# UWB_AOA_with_Display_STM32F103C8T6_V1_1.net
KiCad netlist of a schematic drawn in EAGLE
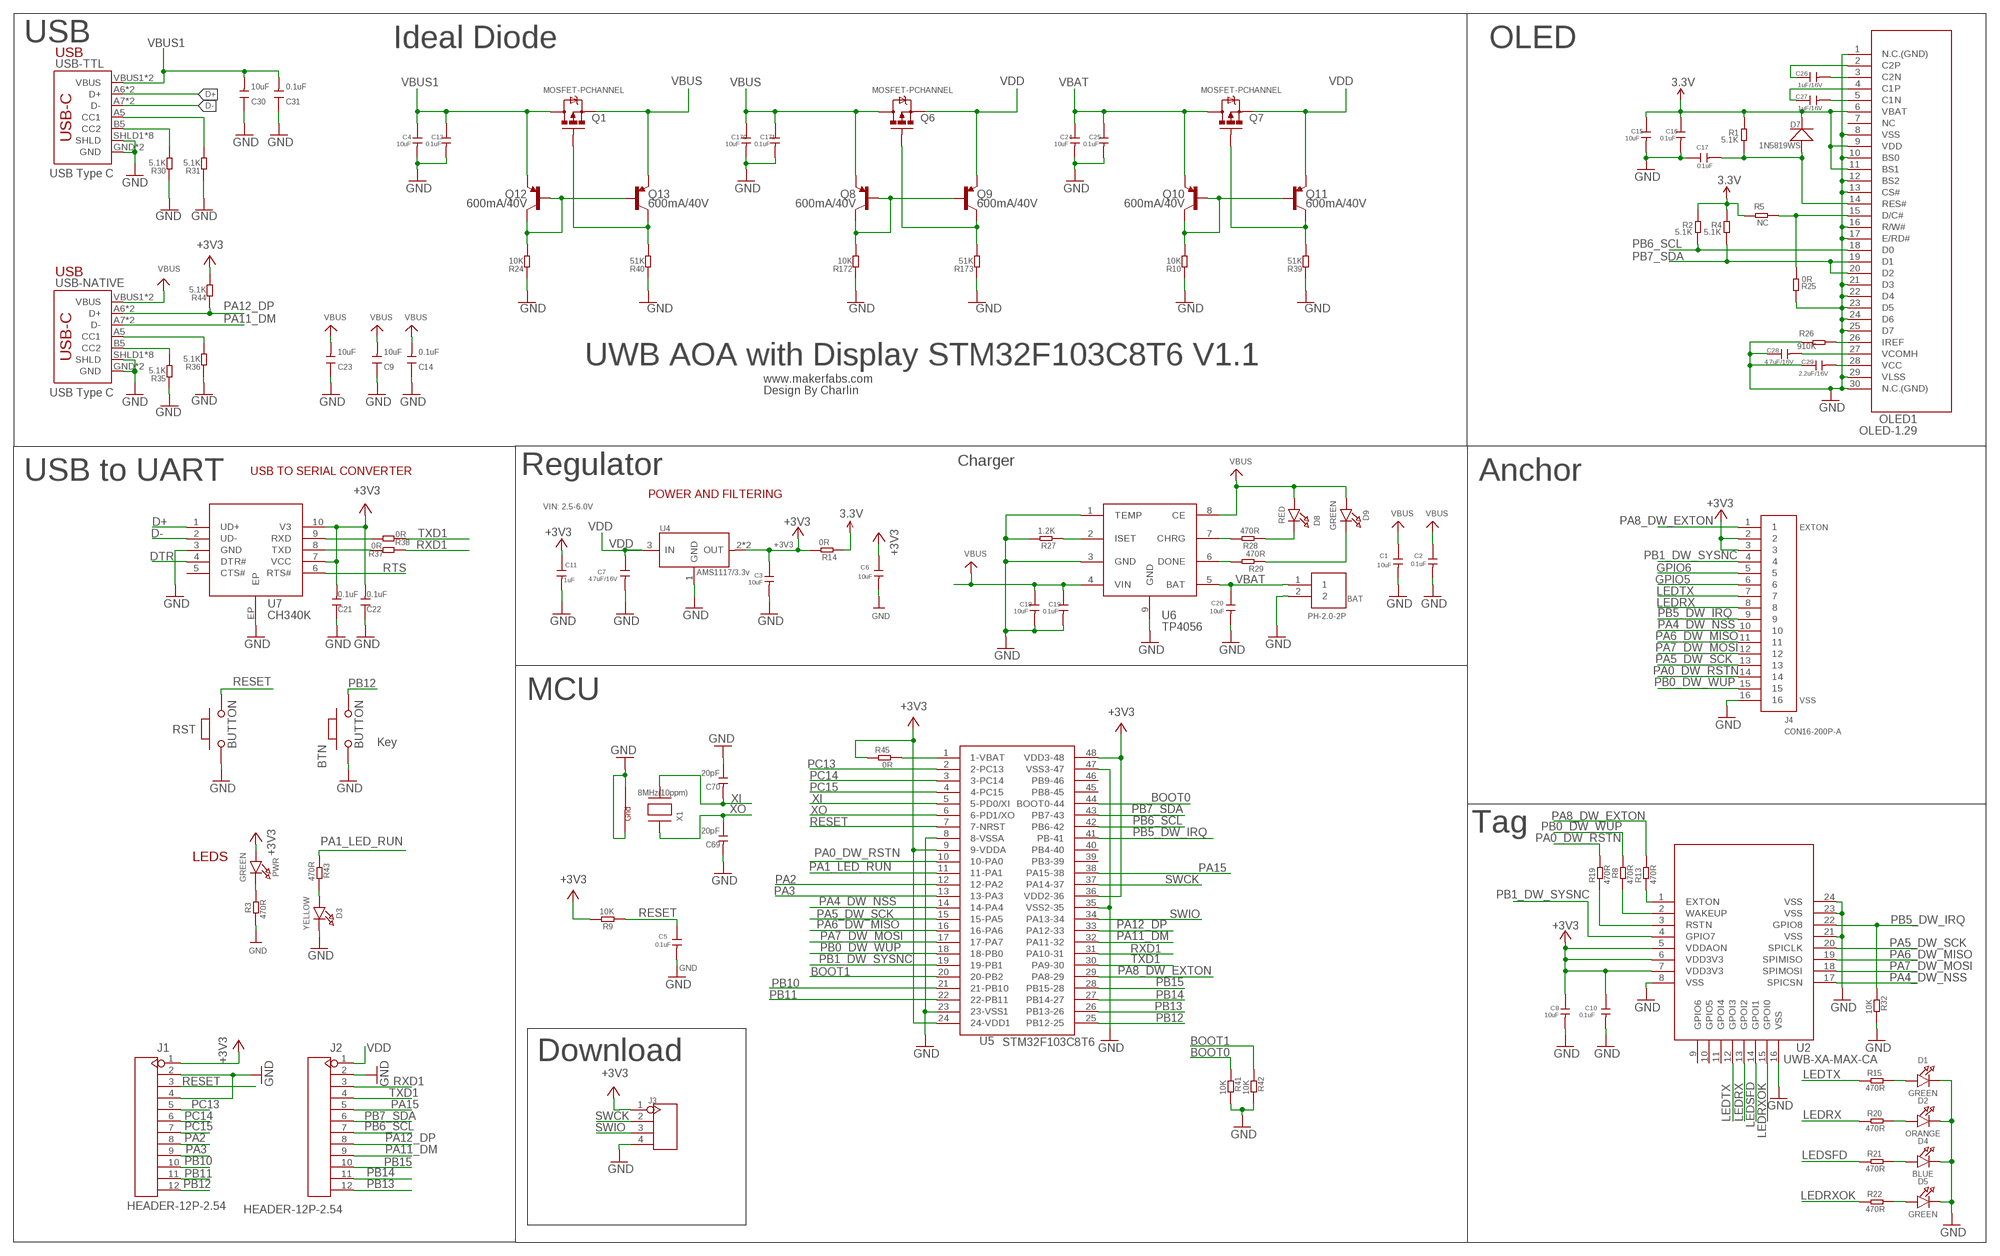
[diagram p0: schematic, sheet 1]

(export (version "E")
  (design (tool "Eeschema 10.0.6"))
  (components
    (comp (ref "BAT")
      (value "PH-2.0-2P")
      (footprint "eagle-import:PH-2.0-2P")
      (libsource (lib "eagle-import") (part "PH-2.0-2P"))
    )
    (comp (ref "BTN")
      (value "BUTTON")
      (footprint "eagle-import:157SW")
      (libsource (lib "eagle-import") (part "PB157"))
    )
    (comp (ref "C1")
      (value "10uF")
      (footprint "eagle-import:C0603")
      (libsource (lib "eagle-import") (part "C-0603"))
    )
    (comp (ref "C2")
      (value "0.1uF")
      (footprint "eagle-import:C0603")
      (libsource (lib "eagle-import") (part "C-0603"))
    )
    (comp (ref "C3")
      (value "10uF")
      (footprint "eagle-import:C0603")
      (libsource (lib "eagle-import") (part "C-0603"))
    )
    (comp (ref "C4")
      (value "10uF")
      (footprint "eagle-import:C0603")
      (libsource (lib "eagle-import") (part "C-0603"))
    )
    (comp (ref "C5")
      (value "0.1uF")
      (footprint "eagle-import:C0603")
      (libsource (lib "eagle-import") (part "C-0603"))
    )
    (comp (ref "C6")
      (value "10uF")
      (footprint "eagle-import:C0603")
      (libsource (lib "eagle-import") (part "C-0603"))
    )
    (comp (ref "C7")
      (value "4.7uF/16V")
      (footprint "eagle-import:C0603")
      (libsource (lib "eagle-import") (part "C-0603"))
    )
    (comp (ref "C8")
      (value "10uF")
      (footprint "eagle-import:C0603")
      (libsource (lib "eagle-import") (part "C-0603"))
    )
    (comp (ref "C9")
      (value "10uF")
      (footprint "eagle-import:DISCRETE_C0603")
      (libsource (lib "eagle-import") (part "DISCRETE_C-0603"))
    )
    (comp (ref "C10")
      (value "0.1uF")
      (footprint "eagle-import:C0603")
      (libsource (lib "eagle-import") (part "C-0603"))
    )
    (comp (ref "C11")
      (value "1uF")
      (footprint "eagle-import:C0603")
      (libsource (lib "eagle-import") (part "C-0603"))
    )
    (comp (ref "C13")
      (value "0.1uF")
      (footprint "eagle-import:C0603")
      (libsource (lib "eagle-import") (part "C-0603"))
    )
    (comp (ref "C14")
      (value "0.1uF")
      (footprint "eagle-import:DISCRETE_C0603")
      (libsource (lib "eagle-import") (part "DISCRETE_C-0603"))
    )
    (comp (ref "C15")
      (value "10uF")
      (footprint "eagle-import:C0603")
      (libsource (lib "eagle-import") (part "C-0603"))
    )
    (comp (ref "C16")
      (value "0.1uF")
      (footprint "eagle-import:C0603")
      (libsource (lib "eagle-import") (part "C-0603"))
    )
    (comp (ref "C17")
      (value "0.1uF")
      (footprint "eagle-import:C0603")
      (libsource (lib "eagle-import") (part "C-0603"))
    )
    (comp (ref "C18")
      (value "10uF")
      (footprint "eagle-import:C0603")
      (libsource (lib "eagle-import") (part "C-0603"))
    )
    (comp (ref "C19")
      (value "0.1uF")
      (footprint "eagle-import:C0603")
      (libsource (lib "eagle-import") (part "C-0603"))
    )
    (comp (ref "C20")
      (value "10uF")
      (footprint "eagle-import:C0603")
      (libsource (lib "eagle-import") (part "C-0603"))
    )
    (comp (ref "C21")
      (value "0.1uF")
      (footprint "eagle-import:DISCRETE_C0603")
      (libsource (lib "eagle-import") (part "DISCRETE_C-0603"))
    )
    (comp (ref "C22")
      (value "0.1uF")
      (footprint "eagle-import:DISCRETE_C0603")
      (libsource (lib "eagle-import") (part "DISCRETE_C-0603"))
    )
    (comp (ref "C23")
      (value "10uF")
      (footprint "eagle-import:DISCRETE_C0603")
      (libsource (lib "eagle-import") (part "DISCRETE_C-0603"))
    )
    (comp (ref "C24")
      (value "10uF")
      (footprint "eagle-import:C0603")
      (libsource (lib "eagle-import") (part "C-0603"))
    )
    (comp (ref "C25")
      (value "0.1uF")
      (footprint "eagle-import:C0603")
      (libsource (lib "eagle-import") (part "C-0603"))
    )
    (comp (ref "C26")
      (value "1uF/16V")
      (footprint "eagle-import:C0603")
      (libsource (lib "eagle-import") (part "C-0603"))
    )
    (comp (ref "C27")
      (value "1uF/16V")
      (footprint "eagle-import:C0603")
      (libsource (lib "eagle-import") (part "C-0603"))
    )
    (comp (ref "C28")
      (value "4.7uF/16V")
      (footprint "eagle-import:C0603")
      (libsource (lib "eagle-import") (part "C-0603"))
    )
    (comp (ref "C29")
      (value "2.2uF/16V")
      (footprint "eagle-import:C0603")
      (libsource (lib "eagle-import") (part "C-0603"))
    )
    (comp (ref "C30")
      (value "10uF")
      (footprint "eagle-import:DISCRETE_C0603")
      (libsource (lib "eagle-import") (part "DISCRETE_C-0603"))
    )
    (comp (ref "C31")
      (value "0.1uF")
      (footprint "eagle-import:DISCRETE_C0603")
      (libsource (lib "eagle-import") (part "DISCRETE_C-0603"))
    )
    (comp (ref "C69")
      (value "20pF")
      (footprint "eagle-import:DISCRETE_C0402")
      (libsource (lib "eagle-import") (part "DISCRETE_C-0402"))
    )
    (comp (ref "C70")
      (value "20pF")
      (footprint "eagle-import:DISCRETE_C0402")
      (libsource (lib "eagle-import") (part "DISCRETE_C-0402"))
    )
    (comp (ref "C170")
      (value "10uF")
      (footprint "eagle-import:C0603")
      (libsource (lib "eagle-import") (part "C-0603"))
    )
    (comp (ref "C171")
      (value "0.1uF")
      (footprint "eagle-import:C0603")
      (libsource (lib "eagle-import") (part "C-0603"))
    )
    (comp (ref "D1")
      (value "GREEN")
      (footprint "eagle-import:CHIPLED_0805_NOOUTLINE")
      (libsource (lib "eagle-import") (part "LED0805_NOOUTLINE"))
    )
    (comp (ref "D2")
      (value "ORANGE")
      (footprint "eagle-import:CHIPLED_0805_NOOUTLINE")
      (libsource (lib "eagle-import") (part "LED0805_NOOUTLINE"))
    )
    (comp (ref "D3")
      (value "YELLOW")
      (footprint "eagle-import:CHIPLED_0805_NOOUTLINE")
      (libsource (lib "eagle-import") (part "LED0805_NOOUTLINE"))
    )
    (comp (ref "D4")
      (value "BLUE")
      (footprint "eagle-import:CHIPLED_0805_NOOUTLINE")
      (libsource (lib "eagle-import") (part "LED0805_NOOUTLINE"))
    )
    (comp (ref "D5")
      (value "GREEN")
      (footprint "eagle-import:CHIPLED_0805_NOOUTLINE")
      (libsource (lib "eagle-import") (part "LED0805_NOOUTLINE"))
    )
    (comp (ref "D7")
      (value "1N5819WS")
      (footprint "eagle-import:SOD323")
      (libsource (lib "eagle-import") (part "D'0805'"))
    )
    (comp (ref "D8")
      (value "RED")
      (footprint "eagle-import:CHIPLED_0805_NOOUTLINE")
      (libsource (lib "eagle-import") (part "LED0805_NOOUTLINE"))
    )
    (comp (ref "D9")
      (value "GREEN")
      (footprint "eagle-import:CHIPLED_0805_NOOUTLINE")
      (libsource (lib "eagle-import") (part "LED0805_NOOUTLINE"))
    )
    (comp (ref "J1")
      (value "HEADER-12P-2.54")
      (footprint "eagle-import:12P-2.54")
      (libsource (lib "eagle-import") (part "HEADER-12P-2.54"))
    )
    (comp (ref "J2")
      (value "HEADER-12P-2.54")
      (footprint "eagle-import:12P-2.54")
      (libsource (lib "eagle-import") (part "HEADER-12P-2.54"))
    )
    (comp (ref "J3")
      (value "HEADER-4P-60/35MILROUND")
      (footprint "eagle-import:4P-65_35ROUND")
      (libsource (lib "eagle-import") (part "HEADER-4P-60/35MILROUND"))
    )
    (comp (ref "J4")
      (value "CON16-200P-A")
      (footprint "eagle-import:THD16-200P-3250L240W430H")
      (libsource (lib "eagle-import") (part "CON16-200P-A"))
    )
    (comp (ref "OLED1")
      (value "OLED-1.29")
      (footprint "eagle-import:OLED-1.29")
      (libsource (lib "eagle-import") (part "OLED-1.29"))
    )
    (comp (ref "PWR")
      (value "GREEN")
      (footprint "eagle-import:CHIPLED_0805_NOOUTLINE")
      (libsource (lib "eagle-import") (part "LED0805_NOOUTLINE"))
    )
    (comp (ref "Q1")
      (value "MOSFET-PCHANNEL")
      (footprint "eagle-import:SOT23-3")
      (fields (field (name "PROD_ID") "TRANS-08285"))
      (libsource (lib "eagle-import") (part "MOSFET-PCHANNEL"))
    )
    (comp (ref "Q6")
      (value "MOSFET-PCHANNEL")
      (footprint "eagle-import:SOT23-3")
      (fields (field (name "PROD_ID") "TRANS-08285"))
      (libsource (lib "eagle-import") (part "MOSFET-PCHANNEL"))
    )
    (comp (ref "Q7")
      (value "MOSFET-PCHANNEL")
      (footprint "eagle-import:SOT23-3")
      (fields (field (name "PROD_ID") "TRANS-08285"))
      (libsource (lib "eagle-import") (part "MOSFET-PCHANNEL"))
    )
    (comp (ref "Q8")
      (value "600mA/40V")
      (footprint "eagle-import:SOT23-3")
      (libsource (lib "eagle-import") (part "TRANS_PNP-MMBT4403"))
    )
    (comp (ref "Q9")
      (value "600mA/40V")
      (footprint "eagle-import:SOT23-3")
      (fields (field (name "PROD_ID") "TRANS-09245"))
      (libsource (lib "eagle-import") (part "TRANS_PNP-MMBT4403"))
    )
    (comp (ref "Q10")
      (value "600mA/40V")
      (footprint "eagle-import:SOT23-3")
      (libsource (lib "eagle-import") (part "TRANS_PNP-MMBT4403"))
    )
    (comp (ref "Q11")
      (value "600mA/40V")
      (footprint "eagle-import:SOT23-3")
      (fields (field (name "PROD_ID") "TRANS-09245"))
      (libsource (lib "eagle-import") (part "TRANS_PNP-MMBT4403"))
    )
    (comp (ref "Q12")
      (value "600mA/40V")
      (footprint "eagle-import:SOT23-3")
      (libsource (lib "eagle-import") (part "TRANS_PNP-MMBT4403"))
    )
    (comp (ref "Q13")
      (value "600mA/40V")
      (footprint "eagle-import:SOT23-3")
      (fields (field (name "PROD_ID") "TRANS-09245"))
      (libsource (lib "eagle-import") (part "TRANS_PNP-MMBT4403"))
    )
    (comp (ref "R1")
      (value "5.1K")
      (footprint "eagle-import:R0603")
      (libsource (lib "eagle-import") (part "R-0603"))
    )
    (comp (ref "R2")
      (value "5.1K")
      (footprint "eagle-import:R0603")
      (libsource (lib "eagle-import") (part "R-0603"))
    )
    (comp (ref "R3")
      (value "470R")
      (footprint "eagle-import:R0603")
      (libsource (lib "eagle-import") (part "R-0603"))
    )
    (comp (ref "R4")
      (value "5.1K")
      (footprint "eagle-import:R0603")
      (libsource (lib "eagle-import") (part "R-0603"))
    )
    (comp (ref "R5")
      (value "NC")
      (footprint "eagle-import:R0603")
      (libsource (lib "eagle-import") (part "R-0603"))
    )
    (comp (ref "R8")
      (value "470R")
      (footprint "eagle-import:R0603")
      (libsource (lib "eagle-import") (part "R-0603"))
    )
    (comp (ref "R9")
      (value "10K")
      (footprint "eagle-import:R0603")
      (libsource (lib "eagle-import") (part "R-0603"))
    )
    (comp (ref "R10")
      (value "10K")
      (footprint "eagle-import:DISCRETE_R0603")
      (libsource (lib "eagle-import") (part "DISCRETE_R-0603"))
    )
    (comp (ref "R13")
      (value "470R")
      (footprint "eagle-import:R0603")
      (libsource (lib "eagle-import") (part "R-0603"))
    )
    (comp (ref "R14")
      (value "0R")
      (footprint "eagle-import:R0603")
      (libsource (lib "eagle-import") (part "R-0603"))
    )
    (comp (ref "R15")
      (value "470R")
      (footprint "eagle-import:R0603")
      (libsource (lib "eagle-import") (part "R-0603"))
    )
    (comp (ref "R19")
      (value "470R")
      (footprint "eagle-import:R0603")
      (libsource (lib "eagle-import") (part "R-0603"))
    )
    (comp (ref "R20")
      (value "470R")
      (footprint "eagle-import:R0603")
      (libsource (lib "eagle-import") (part "R-0603"))
    )
    (comp (ref "R21")
      (value "470R")
      (footprint "eagle-import:R0603")
      (libsource (lib "eagle-import") (part "R-0603"))
    )
    (comp (ref "R22")
      (value "470R")
      (footprint "eagle-import:R0603")
      (libsource (lib "eagle-import") (part "R-0603"))
    )
    (comp (ref "R24")
      (value "10K")
      (footprint "eagle-import:DISCRETE_R0603")
      (libsource (lib "eagle-import") (part "DISCRETE_R-0603"))
    )
    (comp (ref "R25")
      (value "0R")
      (footprint "eagle-import:R0603")
      (libsource (lib "eagle-import") (part "R-0603"))
    )
    (comp (ref "R26")
      (value "910K")
      (footprint "eagle-import:R0603")
      (libsource (lib "eagle-import") (part "R-0603"))
    )
    (comp (ref "R27")
      (value "1.2K")
      (footprint "eagle-import:R0603")
      (libsource (lib "eagle-import") (part "R-0603"))
    )
    (comp (ref "R28")
      (value "470R")
      (footprint "eagle-import:R0603")
      (libsource (lib "eagle-import") (part "R-0603"))
    )
    (comp (ref "R29")
      (value "470R")
      (footprint "eagle-import:R0603")
      (libsource (lib "eagle-import") (part "R-0603"))
    )
    (comp (ref "R30")
      (value "5.1K")
      (footprint "eagle-import:DISCRETE_R0603")
      (libsource (lib "eagle-import") (part "DISCRETE_R-0603"))
    )
    (comp (ref "R31")
      (value "5.1K")
      (footprint "eagle-import:DISCRETE_R0603")
      (libsource (lib "eagle-import") (part "DISCRETE_R-0603"))
    )
    (comp (ref "R32")
      (value "10K")
      (footprint "eagle-import:R0603")
      (libsource (lib "eagle-import") (part "R-0603"))
    )
    (comp (ref "R35")
      (value "5.1K")
      (footprint "eagle-import:DISCRETE_R0603")
      (libsource (lib "eagle-import") (part "DISCRETE_R-0603"))
    )
    (comp (ref "R36")
      (value "5.1K")
      (footprint "eagle-import:DISCRETE_R0603")
      (libsource (lib "eagle-import") (part "DISCRETE_R-0603"))
    )
    (comp (ref "R37")
      (value "0R")
      (footprint "eagle-import:R0603")
      (libsource (lib "eagle-import") (part "R-0603"))
    )
    (comp (ref "R38")
      (value "0R")
      (footprint "eagle-import:R0603")
      (libsource (lib "eagle-import") (part "R-0603"))
    )
    (comp (ref "R39")
      (value "51K")
      (footprint "eagle-import:DISCRETE_R0603")
      (libsource (lib "eagle-import") (part "DISCRETE_R-0603"))
    )
    (comp (ref "R40")
      (value "51K")
      (footprint "eagle-import:DISCRETE_R0603")
      (libsource (lib "eagle-import") (part "DISCRETE_R-0603"))
    )
    (comp (ref "R41")
      (value "10K")
      (footprint "eagle-import:R0603")
      (libsource (lib "eagle-import") (part "R-0603"))
    )
    (comp (ref "R42")
      (value "10K")
      (footprint "eagle-import:R0603")
      (libsource (lib "eagle-import") (part "R-0603"))
    )
    (comp (ref "R43")
      (value "470R")
      (footprint "eagle-import:R0603")
      (libsource (lib "eagle-import") (part "R-0603"))
    )
    (comp (ref "R44")
      (value "5.1K")
      (footprint "eagle-import:DISCRETE_R0603")
      (libsource (lib "eagle-import") (part "DISCRETE_R-0603"))
    )
    (comp (ref "R45")
      (value "0R")
      (footprint "eagle-import:R0603")
      (libsource (lib "eagle-import") (part "R-0603"))
    )
    (comp (ref "R172")
      (value "10K")
      (footprint "eagle-import:DISCRETE_R0603")
      (libsource (lib "eagle-import") (part "DISCRETE_R-0603"))
    )
    (comp (ref "R173")
      (value "51K")
      (footprint "eagle-import:DISCRETE_R0603")
      (libsource (lib "eagle-import") (part "DISCRETE_R-0603"))
    )
    (comp (ref "RST")
      (value "BUTTON")
      (footprint "eagle-import:157SW")
      (libsource (lib "eagle-import") (part "PB157"))
    )
    (comp (ref "U2")
      (value "UWB-XA-MAX-CA")
      (footprint "eagle-import:UWB-X1-MAK-CA")
      (libsource (lib "eagle-import") (part "UWB-XA-MAX-CA"))
    )
    (comp (ref "U4")
      (value "AMS1117/3.3v")
      (footprint "eagle-import:SOT89")
      (libsource (lib "eagle-import") (part "LD1117'SOT89'"))
    )
    (comp (ref "U5")
      (value "STM32F103C8T6")
      (footprint "eagle-import:LQFP48-50P-900L900W160H")
      (libsource (lib "eagle-import") (part "STM32F103C8T6"))
    )
    (comp (ref "U6")
      (value "TP4056")
      (footprint "eagle-import:SOP8-1.27P")
      (libsource (lib "eagle-import") (part "TP4056"))
    )
    (comp (ref "U7")
      (value "CH340K")
      (footprint "eagle-import:ESOP-10-EP-150MIL")
      (libsource (lib "eagle-import") (part "CH340K"))
    )
    (comp (ref "USB-NATIVE")
      (value "USB_C5")
      (footprint "eagle-import:USB-C-16P-5")
      (libsource (lib "eagle-import") (part "USB_C5"))
    )
    (comp (ref "USB-TTL")
      (value "USB_C5")
      (footprint "eagle-import:USB-C-16P-5")
      (libsource (lib "eagle-import") (part "USB_C5"))
    )
    (comp (ref "X1")
      (value "8MHz(10ppm)")
      (footprint "eagle-import:NX3225")
      (libsource (lib "eagle-import") (part "XTAL-4-3225"))
    )
  )
  (nets
    (net (code "1") (name "+3V3") (class "Default")
      (node (ref "C10") (pin "1") (pinfunction "1_1") (pintype "passive"))
      (node (ref "C11") (pin "1") (pinfunction "1_1") (pintype "passive"))
      (node (ref "C21") (pin "2") (pinfunction "2_2") (pintype "passive"))
      (node (ref "C22") (pin "2") (pinfunction "2_2") (pintype "passive"))
      (node (ref "C3") (pin "1") (pinfunction "1_1") (pintype "passive"))
      (node (ref "C6") (pin "1") (pinfunction "1_1") (pintype "passive"))
      (node (ref "C8") (pin "1") (pinfunction "1_1") (pintype "passive"))
      (node (ref "J1") (pin "1") (pinfunction "1_1") (pintype "bidirectional"))
      (node (ref "J3") (pin "1") (pinfunction "P$1_1") (pintype "bidirectional"))
      (node (ref "J4") (pin "2") (pinfunction "2_2") (pintype "bidirectional"))
      (node (ref "J4") (pin "3") (pinfunction "3_3") (pintype "bidirectional"))
      (node (ref "PWR") (pin "A") (pinfunction "A_A") (pintype "passive"))
      (node (ref "R14") (pin "2") (pinfunction "2_2") (pintype "passive"))
      (node (ref "R44") (pin "2") (pinfunction "2_2") (pintype "passive"))
      (node (ref "R45") (pin "1") (pinfunction "1_1") (pintype "passive"))
      (node (ref "R9") (pin "2") (pinfunction "2_2") (pintype "passive"))
      (node (ref "U2") (pin "5") (pinfunction "VDDAON_5") (pintype "bidirectional"))
      (node (ref "U2") (pin "6") (pinfunction "VDD3V3_6") (pintype "bidirectional"))
      (node (ref "U2") (pin "7") (pinfunction "VDD3V3_7") (pintype "bidirectional"))
      (node (ref "U4") (pin "2") (pinfunction "OUT_2") (pintype "bidirectional"))
      (node (ref "U4") (pin "4") (pinfunction "OUT_4") (pintype "bidirectional"))
      (node (ref "U5") (pin "24") (pinfunction "24-VDD1_24") (pintype "bidirectional"))
      (node (ref "U5") (pin "36") (pinfunction "VDD2-36_36") (pintype "bidirectional"))
      (node (ref "U5") (pin "48") (pinfunction "VDD3-48_48") (pintype "bidirectional"))
      (node (ref "U5") (pin "9") (pinfunction "9-VDDA_9") (pintype "bidirectional"))
      (node (ref "U7") (pin "10") (pinfunction "V3_10") (pintype "bidirectional"))
      (node (ref "U7") (pin "7") (pinfunction "VCC_7") (pintype "bidirectional"))
    )
    (net (code "2") (name "/BOOT0") (class "Default")
      (node (ref "R41") (pin "1") (pinfunction "1_1") (pintype "passive"))
      (node (ref "U5") (pin "44") (pinfunction "BOOT0-44_44") (pintype "bidirectional"))
    )
    (net (code "3") (name "/BOOT1") (class "Default")
      (node (ref "R42") (pin "1") (pinfunction "1_1") (pintype "passive"))
      (node (ref "U5") (pin "20") (pinfunction "20-PB2_20") (pintype "bidirectional"))
    )
    (net (code "4") (name "/DTR") (class "Default")
      (node (ref "U7") (pin "4") (pinfunction "DTR#_4") (pintype "bidirectional"))
    )
    (net (code "5") (name "/GPIO5") (class "Default")
      (node (ref "J4") (pin "6") (pinfunction "6_6") (pintype "bidirectional"))
    )
    (net (code "6") (name "/GPIO6") (class "Default")
      (node (ref "J4") (pin "5") (pinfunction "5_5") (pintype "bidirectional"))
    )
    (net (code "7") (name "/LEDRX") (class "Default")
      (node (ref "J4") (pin "8") (pinfunction "8_8") (pintype "bidirectional"))
      (node (ref "R20") (pin "1") (pinfunction "1_1") (pintype "passive"))
      (node (ref "U2") (pin "13") (pinfunction "GPOI2_13") (pintype "bidirectional"))
    )
    (net (code "8") (name "/LEDRXOK") (class "Default")
      (node (ref "R22") (pin "1") (pinfunction "1_1") (pintype "passive"))
      (node (ref "U2") (pin "15") (pinfunction "GPOI0_15") (pintype "bidirectional"))
    )
    (net (code "9") (name "/LEDSFD") (class "Default")
      (node (ref "R21") (pin "1") (pinfunction "1_1") (pintype "passive"))
      (node (ref "U2") (pin "14") (pinfunction "GPOI1_14") (pintype "bidirectional"))
    )
    (net (code "10") (name "/LEDTX") (class "Default")
      (node (ref "J4") (pin "7") (pinfunction "7_7") (pintype "bidirectional"))
      (node (ref "R15") (pin "1") (pinfunction "1_1") (pintype "passive"))
      (node (ref "U2") (pin "12") (pinfunction "GPOI3_12") (pintype "bidirectional"))
    )
    (net (code "11") (name "/PA0_DW_RSTN") (class "Default")
      (node (ref "J4") (pin "14") (pinfunction "14_14") (pintype "bidirectional"))
      (node (ref "R19") (pin "2") (pinfunction "2_2") (pintype "passive"))
      (node (ref "U5") (pin "10") (pinfunction "10-PA0_10") (pintype "bidirectional"))
    )
    (net (code "12") (name "/PA1_LED_RUN") (class "Default")
      (node (ref "R43") (pin "1") (pinfunction "1_1") (pintype "passive"))
      (node (ref "U5") (pin "11") (pinfunction "11-PA1_11") (pintype "bidirectional"))
    )
    (net (code "13") (name "/PA2") (class "Default")
      (node (ref "J1") (pin "8") (pinfunction "8_8") (pintype "bidirectional"))
      (node (ref "U5") (pin "12") (pinfunction "12-PA2_12") (pintype "bidirectional"))
    )
    (net (code "14") (name "/PA3") (class "Default")
      (node (ref "J1") (pin "9") (pinfunction "9_9") (pintype "bidirectional"))
      (node (ref "U5") (pin "13") (pinfunction "13-PA3_13") (pintype "bidirectional"))
    )
    (net (code "15") (name "/PA4_DW_NSS") (class "Default")
      (node (ref "J4") (pin "10") (pinfunction "10_10") (pintype "bidirectional"))
      (node (ref "U2") (pin "17") (pinfunction "SPICSN_17") (pintype "bidirectional"))
      (node (ref "U5") (pin "14") (pinfunction "14-PA4_14") (pintype "bidirectional"))
    )
    (net (code "16") (name "/PA5_DW_SCK") (class "Default")
      (node (ref "J4") (pin "13") (pinfunction "13_13") (pintype "bidirectional"))
      (node (ref "U2") (pin "20") (pinfunction "SPICLK_20") (pintype "bidirectional"))
      (node (ref "U5") (pin "15") (pinfunction "15-PA5_15") (pintype "bidirectional"))
    )
    (net (code "17") (name "/PA6_DW_MISO") (class "Default")
      (node (ref "J4") (pin "11") (pinfunction "11_11") (pintype "bidirectional"))
      (node (ref "U2") (pin "19") (pinfunction "SPIMISO_19") (pintype "bidirectional"))
      (node (ref "U5") (pin "16") (pinfunction "16-PA6_16") (pintype "bidirectional"))
    )
    (net (code "18") (name "/PA7_DW_MOSI") (class "Default")
      (node (ref "J4") (pin "12") (pinfunction "12_12") (pintype "bidirectional"))
      (node (ref "U2") (pin "18") (pinfunction "SPIMOSI_18") (pintype "bidirectional"))
      (node (ref "U5") (pin "17") (pinfunction "17-PA7_17") (pintype "bidirectional"))
    )
    (net (code "19") (name "/PA8_DW_EXTON") (class "Default")
      (node (ref "J4") (pin "1") (pinfunction "1_1") (pintype "bidirectional"))
      (node (ref "R13") (pin "2") (pinfunction "2_2") (pintype "passive"))
      (node (ref "U5") (pin "29") (pinfunction "PA8-29_29") (pintype "bidirectional"))
    )
    (net (code "20") (name "/PA11_DM") (class "Default")
      (node (ref "J2") (pin "9") (pinfunction "9_9") (pintype "bidirectional"))
      (node (ref "U5") (pin "32") (pinfunction "PA11-32_32") (pintype "bidirectional"))
      (node (ref "USB-NATIVE") (pin "A7") (pinfunction "D-_A7") (pintype "bidirectional"))
      (node (ref "USB-NATIVE") (pin "B7") (pinfunction "D-_B7") (pintype "bidirectional"))
    )
    (net (code "21") (name "/PA12_DP") (class "Default")
      (node (ref "J2") (pin "8") (pinfunction "8_8") (pintype "bidirectional"))
      (node (ref "R44") (pin "1") (pinfunction "1_1") (pintype "passive"))
      (node (ref "U5") (pin "33") (pinfunction "PA12-33_33") (pintype "bidirectional"))
      (node (ref "USB-NATIVE") (pin "A6") (pinfunction "D+_A6") (pintype "bidirectional"))
      (node (ref "USB-NATIVE") (pin "B6") (pinfunction "D+_B6") (pintype "bidirectional"))
    )
    (net (code "22") (name "/PA15") (class "Default")
      (node (ref "J2") (pin "5") (pinfunction "5_5") (pintype "bidirectional"))
      (node (ref "U5") (pin "38") (pinfunction "PA15-38_38") (pintype "bidirectional"))
    )
    (net (code "23") (name "/PB0_DW_WUP") (class "Default")
      (node (ref "J4") (pin "15") (pinfunction "15_15") (pintype "bidirectional"))
      (node (ref "R8") (pin "2") (pinfunction "2_2") (pintype "passive"))
      (node (ref "U5") (pin "18") (pinfunction "18-PB0_18") (pintype "bidirectional"))
    )
    (net (code "24") (name "/PB1_DW_SYSNC") (class "Default")
      (node (ref "J4") (pin "4") (pinfunction "4_4") (pintype "bidirectional"))
      (node (ref "U2") (pin "4") (pinfunction "GPIO7_4") (pintype "bidirectional"))
      (node (ref "U5") (pin "19") (pinfunction "19-PB1_19") (pintype "bidirectional"))
    )
    (net (code "25") (name "/PB5_DW_IRQ") (class "Default")
      (node (ref "J4") (pin "9") (pinfunction "9_9") (pintype "bidirectional"))
      (node (ref "R32") (pin "1") (pinfunction "1_1") (pintype "passive"))
      (node (ref "U2") (pin "22") (pinfunction "GPIO8_22") (pintype "bidirectional"))
      (node (ref "U5") (pin "41") (pinfunction "PB-41_41") (pintype "bidirectional"))
    )
    (net (code "26") (name "/PB6_SCL") (class "Default")
      (node (ref "J2") (pin "7") (pinfunction "7_7") (pintype "bidirectional"))
      (node (ref "OLED1") (pin "18") (pinfunction "D0_18") (pintype "bidirectional"))
      (node (ref "R2") (pin "1") (pinfunction "1_1") (pintype "passive"))
      (node (ref "U5") (pin "42") (pinfunction "PB6-42_42") (pintype "bidirectional"))
    )
    (net (code "27") (name "/PB7_SDA") (class "Default")
      (node (ref "J2") (pin "6") (pinfunction "6_6") (pintype "bidirectional"))
      (node (ref "OLED1") (pin "19") (pinfunction "D1_19") (pintype "bidirectional"))
      (node (ref "OLED1") (pin "20") (pinfunction "D2_20") (pintype "bidirectional"))
      (node (ref "R4") (pin "1") (pinfunction "1_1") (pintype "passive"))
      (node (ref "U5") (pin "43") (pinfunction "PB7-43_43") (pintype "bidirectional"))
    )
    (net (code "28") (name "/PB10") (class "Default")
      (node (ref "J1") (pin "10") (pinfunction "10_10") (pintype "bidirectional"))
      (node (ref "U5") (pin "21") (pinfunction "21-PB10_21") (pintype "bidirectional"))
    )
    (net (code "29") (name "/PB11") (class "Default")
      (node (ref "J1") (pin "11") (pinfunction "11_11") (pintype "bidirectional"))
      (node (ref "U5") (pin "22") (pinfunction "22-PB11_22") (pintype "bidirectional"))
    )
    (net (code "30") (name "/PB12") (class "Default")
      (node (ref "BTN") (pin "2") (pinfunction "2_2") (pintype "passive"))
      (node (ref "J1") (pin "12") (pinfunction "12_12") (pintype "bidirectional"))
      (node (ref "U5") (pin "25") (pinfunction "PB12-25_25") (pintype "bidirectional"))
    )
    (net (code "31") (name "/PB13") (class "Default")
      (node (ref "J2") (pin "12") (pinfunction "12_12") (pintype "bidirectional"))
      (node (ref "U5") (pin "26") (pinfunction "PB13-26_26") (pintype "bidirectional"))
    )
    (net (code "32") (name "/PB14") (class "Default")
      (node (ref "J2") (pin "11") (pinfunction "11_11") (pintype "bidirectional"))
      (node (ref "U5") (pin "27") (pinfunction "PB14-27_27") (pintype "bidirectional"))
    )
    (net (code "33") (name "/PB15") (class "Default")
      (node (ref "J2") (pin "10") (pinfunction "10_10") (pintype "bidirectional"))
      (node (ref "U5") (pin "28") (pinfunction "PB15-28_28") (pintype "bidirectional"))
    )
    (net (code "34") (name "/PC13") (class "Default")
      (node (ref "J1") (pin "5") (pinfunction "5_5") (pintype "bidirectional"))
      (node (ref "U5") (pin "2") (pinfunction "2-PC13_2") (pintype "bidirectional"))
    )
    (net (code "35") (name "/PC14") (class "Default")
      (node (ref "J1") (pin "6") (pinfunction "6_6") (pintype "bidirectional"))
      (node (ref "U5") (pin "3") (pinfunction "3-PC14_3") (pintype "bidirectional"))
    )
    (net (code "36") (name "/PC15") (class "Default")
      (node (ref "J1") (pin "7") (pinfunction "7_7") (pintype "bidirectional"))
      (node (ref "U5") (pin "4") (pinfunction "4-PC15_4") (pintype "bidirectional"))
    )
    (net (code "37") (name "/RESET") (class "Default")
      (node (ref "C5") (pin "1") (pinfunction "1_1") (pintype "passive"))
      (node (ref "J1") (pin "3") (pinfunction "3_3") (pintype "bidirectional"))
      (node (ref "R9") (pin "1") (pinfunction "1_1") (pintype "passive"))
      (node (ref "RST") (pin "2") (pinfunction "2_2") (pintype "passive"))
      (node (ref "U5") (pin "7") (pinfunction "7-NRST_7") (pintype "bidirectional"))
    )
    (net (code "38") (name "/RTS") (class "Default")
      (node (ref "U7") (pin "6") (pinfunction "RTS#_6") (pintype "bidirectional"))
    )
    (net (code "39") (name "/RXD1") (class "Default")
      (node (ref "J2") (pin "3") (pinfunction "3_3") (pintype "bidirectional"))
      (node (ref "R37") (pin "1") (pinfunction "1_1") (pintype "passive"))
      (node (ref "U5") (pin "31") (pinfunction "PA10-31_31") (pintype "bidirectional"))
    )
    (net (code "40") (name "/SWCK") (class "Default")
      (node (ref "J3") (pin "2") (pinfunction "P$2_2") (pintype "bidirectional"))
      (node (ref "U5") (pin "37") (pinfunction "PA14-37_37") (pintype "bidirectional"))
    )
    (net (code "41") (name "/SWIO") (class "Default")
      (node (ref "J3") (pin "3") (pinfunction "P$3_3") (pintype "bidirectional"))
      (node (ref "U5") (pin "34") (pinfunction "PA13-34_34") (pintype "bidirectional"))
    )
    (net (code "42") (name "/TXD1") (class "Default")
      (node (ref "J2") (pin "4") (pinfunction "4_4") (pintype "bidirectional"))
      (node (ref "R38") (pin "1") (pinfunction "1_1") (pintype "passive"))
      (node (ref "U5") (pin "30") (pinfunction "PA9-30_30") (pintype "bidirectional"))
    )
    (net (code "43") (name "/VBAT") (class "Default")
      (node (ref "BAT") (pin "1") (pinfunction "1_1") (pintype "bidirectional"))
      (node (ref "C20") (pin "1") (pinfunction "1_1") (pintype "passive"))
      (node (ref "C24") (pin "1") (pinfunction "1_1") (pintype "passive"))
      (node (ref "C25") (pin "1") (pinfunction "1_1") (pintype "passive"))
      (node (ref "Q10") (pin "2") (pinfunction "E_2") (pintype "passive"))
      (node (ref "Q7") (pin "3") (pinfunction "D_3") (pintype "passive"))
      (node (ref "U6") (pin "5") (pinfunction "BAT_5") (pintype "bidirectional"))
    )
    (net (code "44") (name "/VBUS1") (class "Default")
      (node (ref "C13") (pin "1") (pinfunction "1_1") (pintype "passive"))
      (node (ref "C30") (pin "2") (pinfunction "2_2") (pintype "passive"))
      (node (ref "C31") (pin "2") (pinfunction "2_2") (pintype "passive"))
      (node (ref "C4") (pin "1") (pinfunction "1_1") (pintype "passive"))
      (node (ref "Q1") (pin "3") (pinfunction "D_3") (pintype "passive"))
      (node (ref "Q12") (pin "2") (pinfunction "E_2") (pintype "passive"))
      (node (ref "USB-TTL") (pin "VBUS1") (pinfunction "VBUS_VBUS1") (pintype "bidirectional"))
      (node (ref "USB-TTL") (pin "VBUS2") (pinfunction "VBUS_VBUS2") (pintype "bidirectional"))
    )
    (net (code "45") (name "/VDD") (class "Default")
      (node (ref "C7") (pin "1") (pinfunction "1_1") (pintype "passive"))
      (node (ref "J2") (pin "1") (pinfunction "1_1") (pintype "bidirectional"))
      (node (ref "Q11") (pin "2") (pinfunction "E_2") (pintype "passive"))
      (node (ref "Q6") (pin "2") (pinfunction "S_2") (pintype "passive"))
      (node (ref "Q7") (pin "2") (pinfunction "S_2") (pintype "passive"))
      (node (ref "Q9") (pin "2") (pinfunction "E_2") (pintype "passive"))
      (node (ref "U4") (pin "3") (pinfunction "IN_3") (pintype "bidirectional"))
    )
    (net (code "46") (name "/XI") (class "Default")
      (node (ref "C70") (pin "2") (pinfunction "2_2") (pintype "passive"))
      (node (ref "U5") (pin "5") (pinfunction "5-PD0/XI_5") (pintype "bidirectional"))
      (node (ref "X1") (pin "3") (pinfunction "X2_3") (pintype "bidirectional"))
    )
    (net (code "47") (name "/XO") (class "Default")
      (node (ref "C69") (pin "1") (pinfunction "1_1") (pintype "passive"))
      (node (ref "U5") (pin "6") (pinfunction "6-PD1/XO_6") (pintype "bidirectional"))
      (node (ref "X1") (pin "1") (pinfunction "X1_1") (pintype "bidirectional"))
    )
    (net (code "48") (name "3.3V") (class "Default")
      (node (ref "C15") (pin "1") (pinfunction "1_1") (pintype "passive"))
      (node (ref "C16") (pin "1") (pinfunction "1_1") (pintype "passive"))
      (node (ref "D7") (pin "-") (pinfunction "-_-") (pintype "passive"))
      (node (ref "OLED1") (pin "11") (pinfunction "BS1_11") (pintype "bidirectional"))
      (node (ref "OLED1") (pin "6") (pinfunction "VBAT_6") (pintype "bidirectional"))
      (node (ref "OLED1") (pin "9") (pinfunction "VDD_9") (pintype "bidirectional"))
      (node (ref "R1") (pin "2") (pinfunction "2_2") (pintype "passive"))
      (node (ref "R14") (pin "1") (pinfunction "1_1") (pintype "passive"))
      (node (ref "R2") (pin "2") (pinfunction "2_2") (pintype "passive"))
      (node (ref "R4") (pin "2") (pinfunction "2_2") (pintype "passive"))
      (node (ref "R5") (pin "2") (pinfunction "2_2") (pintype "passive"))
    )
    (net (code "49") (name "D+") (class "Default")
      (node (ref "U7") (pin "1") (pinfunction "UD+_1") (pintype "bidirectional"))
      (node (ref "USB-TTL") (pin "A6") (pinfunction "D+_A6") (pintype "bidirectional"))
      (node (ref "USB-TTL") (pin "B6") (pinfunction "D+_B6") (pintype "bidirectional"))
    )
    (net (code "50") (name "D-") (class "Default")
      (node (ref "U7") (pin "2") (pinfunction "UD-_2") (pintype "bidirectional"))
      (node (ref "USB-TTL") (pin "A7") (pinfunction "D-_A7") (pintype "bidirectional"))
      (node (ref "USB-TTL") (pin "B7") (pinfunction "D-_B7") (pintype "bidirectional"))
    )
    (net (code "51") (name "GND") (class "Default")
      (node (ref "BAT") (pin "2") (pinfunction "2_2") (pintype "bidirectional"))
      (node (ref "BTN") (pin "1") (pinfunction "1_1") (pintype "passive"))
      (node (ref "C1") (pin "2") (pinfunction "2_2") (pintype "passive"))
      (node (ref "C10") (pin "2") (pinfunction "2_2") (pintype "passive"))
      (node (ref "C11") (pin "2") (pinfunction "2_2") (pintype "passive"))
      (node (ref "C13") (pin "2") (pinfunction "2_2") (pintype "passive"))
      (node (ref "C14") (pin "1") (pinfunction "1_1") (pintype "passive"))
      (node (ref "C15") (pin "2") (pinfunction "2_2") (pintype "passive"))
      (node (ref "C16") (pin "2") (pinfunction "2_2") (pintype "passive"))
      (node (ref "C17") (pin "1") (pinfunction "1_1") (pintype "passive"))
      (node (ref "C170") (pin "2") (pinfunction "2_2") (pintype "passive"))
      (node (ref "C171") (pin "2") (pinfunction "2_2") (pintype "passive"))
      (node (ref "C18") (pin "2") (pinfunction "2_2") (pintype "passive"))
      (node (ref "C19") (pin "2") (pinfunction "2_2") (pintype "passive"))
      (node (ref "C2") (pin "2") (pinfunction "2_2") (pintype "passive"))
      (node (ref "C20") (pin "2") (pinfunction "2_2") (pintype "passive"))
      (node (ref "C21") (pin "1") (pinfunction "1_1") (pintype "passive"))
      (node (ref "C22") (pin "1") (pinfunction "1_1") (pintype "passive"))
      (node (ref "C23") (pin "1") (pinfunction "1_1") (pintype "passive"))
      (node (ref "C24") (pin "2") (pinfunction "2_2") (pintype "passive"))
      (node (ref "C25") (pin "2") (pinfunction "2_2") (pintype "passive"))
      (node (ref "C28") (pin "1") (pinfunction "1_1") (pintype "passive"))
      (node (ref "C29") (pin "1") (pinfunction "1_1") (pintype "passive"))
      (node (ref "C3") (pin "2") (pinfunction "2_2") (pintype "passive"))
      (node (ref "C30") (pin "1") (pinfunction "1_1") (pintype "passive"))
      (node (ref "C31") (pin "1") (pinfunction "1_1") (pintype "passive"))
      (node (ref "C4") (pin "2") (pinfunction "2_2") (pintype "passive"))
      (node (ref "C5") (pin "2") (pinfunction "2_2") (pintype "passive"))
      (node (ref "C6") (pin "2") (pinfunction "2_2") (pintype "passive"))
      (node (ref "C69") (pin "2") (pinfunction "2_2") (pintype "passive"))
      (node (ref "C7") (pin "2") (pinfunction "2_2") (pintype "passive"))
      (node (ref "C70") (pin "1") (pinfunction "1_1") (pintype "passive"))
      (node (ref "C8") (pin "2") (pinfunction "2_2") (pintype "passive"))
      (node (ref "C9") (pin "1") (pinfunction "1_1") (pintype "passive"))
      (node (ref "D1") (pin "C") (pinfunction "C_C") (pintype "passive"))
      (node (ref "D2") (pin "C") (pinfunction "C_C") (pintype "passive"))
      (node (ref "D3") (pin "C") (pinfunction "C_C") (pintype "passive"))
      (node (ref "D4") (pin "C") (pinfunction "C_C") (pintype "passive"))
      (node (ref "D5") (pin "C") (pinfunction "C_C") (pintype "passive"))
      (node (ref "J1") (pin "2") (pinfunction "2_2") (pintype "bidirectional"))
      (node (ref "J1") (pin "4") (pinfunction "4_4") (pintype "bidirectional"))
      (node (ref "J2") (pin "2") (pinfunction "2_2") (pintype "bidirectional"))
      (node (ref "J3") (pin "4") (pinfunction "P$4_4") (pintype "bidirectional"))
      (node (ref "J4") (pin "16") (pinfunction "16_16") (pintype "bidirectional"))
      (node (ref "OLED1") (pin "1") (pinfunction "N.C.(GND)_1") (pintype "bidirectional"))
      (node (ref "OLED1") (pin "10") (pinfunction "BS0_10") (pintype "bidirectional"))
      (node (ref "OLED1") (pin "12") (pinfunction "BS2_12") (pintype "bidirectional"))
      (node (ref "OLED1") (pin "13") (pinfunction "CS#_13") (pintype "bidirectional"))
      (node (ref "OLED1") (pin "16") (pinfunction "R/W#_16") (pintype "bidirectional"))
      (node (ref "OLED1") (pin "17") (pinfunction "E/RD#_17") (pintype "bidirectional"))
      (node (ref "OLED1") (pin "21") (pinfunction "D3_21") (pintype "bidirectional"))
      (node (ref "OLED1") (pin "22") (pinfunction "D4_22") (pintype "bidirectional"))
      (node (ref "OLED1") (pin "23") (pinfunction "D5_23") (pintype "bidirectional"))
      (node (ref "OLED1") (pin "24") (pinfunction "D6_24") (pintype "bidirectional"))
      (node (ref "OLED1") (pin "25") (pinfunction "D7_25") (pintype "bidirectional"))
      (node (ref "OLED1") (pin "29") (pinfunction "VLSS_29") (pintype "bidirectional"))
      (node (ref "OLED1") (pin "30") (pinfunction "N.C.(GND)_30") (pintype "bidirectional"))
      (node (ref "OLED1") (pin "8") (pinfunction "VSS_8") (pintype "bidirectional"))
      (node (ref "R10") (pin "1") (pinfunction "1_1") (pintype "passive"))
      (node (ref "R172") (pin "1") (pinfunction "1_1") (pintype "passive"))
      (node (ref "R173") (pin "1") (pinfunction "1_1") (pintype "passive"))
      (node (ref "R24") (pin "1") (pinfunction "1_1") (pintype "passive"))
      (node (ref "R25") (pin "2") (pinfunction "2_2") (pintype "passive"))
      (node (ref "R26") (pin "2") (pinfunction "2_2") (pintype "passive"))
      (node (ref "R27") (pin "2") (pinfunction "2_2") (pintype "passive"))
      (node (ref "R3") (pin "1") (pinfunction "1_1") (pintype "passive"))
      (node (ref "R30") (pin "1") (pinfunction "1_1") (pintype "passive"))
      (node (ref "R31") (pin "1") (pinfunction "1_1") (pintype "passive"))
      (node (ref "R32") (pin "2") (pinfunction "2_2") (pintype "passive"))
      (node (ref "R35") (pin "1") (pinfunction "1_1") (pintype "passive"))
      (node (ref "R36") (pin "1") (pinfunction "1_1") (pintype "passive"))
      (node (ref "R39") (pin "1") (pinfunction "1_1") (pintype "passive"))
      (node (ref "R40") (pin "1") (pinfunction "1_1") (pintype "passive"))
      (node (ref "R41") (pin "2") (pinfunction "2_2") (pintype "passive"))
      (node (ref "R42") (pin "2") (pinfunction "2_2") (pintype "passive"))
      (node (ref "RST") (pin "1") (pinfunction "1_1") (pintype "passive"))
      (node (ref "U2") (pin "16") (pinfunction "VSS_16") (pintype "bidirectional"))
      (node (ref "U2") (pin "21") (pinfunction "VSS_21") (pintype "bidirectional"))
      (node (ref "U2") (pin "23") (pinfunction "VSS_23") (pintype "bidirectional"))
      (node (ref "U2") (pin "24") (pinfunction "VSS_24") (pintype "bidirectional"))
      (node (ref "U2") (pin "8") (pinfunction "VSS_8") (pintype "bidirectional"))
      (node (ref "U4") (pin "1") (pinfunction "GND_1") (pintype "bidirectional"))
      (node (ref "U5") (pin "23") (pinfunction "23-VSS1_23") (pintype "bidirectional"))
      (node (ref "U5") (pin "35") (pinfunction "VSS2-35_35") (pintype "bidirectional"))
      (node (ref "U5") (pin "47") (pinfunction "VSS3-47_47") (pintype "bidirectional"))
      (node (ref "U5") (pin "8") (pinfunction "8-VSSA_8") (pintype "bidirectional"))
      (node (ref "U6") (pin "1") (pinfunction "TEMP_1") (pintype "bidirectional"))
      (node (ref "U6") (pin "3") (pinfunction "GND_3") (pintype "bidirectional"))
      (node (ref "U6") (pin "9") (pinfunction "GND_9") (pintype "bidirectional"))
      (node (ref "U7") (pin "3") (pinfunction "GND_3") (pintype "bidirectional"))
      (node (ref "U7") (pin "EP") (pinfunction "EP_EP") (pintype "bidirectional"))
      (node (ref "USB-NATIVE") (pin "GND") (pinfunction "GND_GND") (pintype "bidirectional"))
      (node (ref "USB-NATIVE") (pin "GND2") (pinfunction "GND_GND2") (pintype "bidirectional"))
      (node (ref "USB-NATIVE") (pin "SHLD1") (pinfunction "SHLD_SHLD1") (pintype "bidirectional"))
      (node (ref "USB-NATIVE") (pin "SHLD2") (pinfunction "SHLD_SHLD2") (pintype "bidirectional"))
      (node (ref "USB-NATIVE") (pin "SHLD3") (pinfunction "SHLD_SHLD3") (pintype "bidirectional"))
      (node (ref "USB-NATIVE") (pin "SHLD4") (pinfunction "SHLD_SHLD4") (pintype "bidirectional"))
      (node (ref "USB-NATIVE") (pin "SHLD5") (pinfunction "SHLD_SHLD5") (pintype "bidirectional"))
      (node (ref "USB-NATIVE") (pin "SHLD6") (pinfunction "SHLD_SHLD6") (pintype "bidirectional"))
      (node (ref "USB-NATIVE") (pin "SHLD7") (pinfunction "SHLD_SHLD7") (pintype "bidirectional"))
      (node (ref "USB-NATIVE") (pin "SHLD8") (pinfunction "SHLD_SHLD8") (pintype "bidirectional"))
      (node (ref "USB-TTL") (pin "GND") (pinfunction "GND_GND") (pintype "bidirectional"))
      (node (ref "USB-TTL") (pin "GND2") (pinfunction "GND_GND2") (pintype "bidirectional"))
      (node (ref "USB-TTL") (pin "SHLD1") (pinfunction "SHLD_SHLD1") (pintype "bidirectional"))
      (node (ref "USB-TTL") (pin "SHLD2") (pinfunction "SHLD_SHLD2") (pintype "bidirectional"))
      (node (ref "USB-TTL") (pin "SHLD3") (pinfunction "SHLD_SHLD3") (pintype "bidirectional"))
      (node (ref "USB-TTL") (pin "SHLD4") (pinfunction "SHLD_SHLD4") (pintype "bidirectional"))
      (node (ref "USB-TTL") (pin "SHLD5") (pinfunction "SHLD_SHLD5") (pintype "bidirectional"))
      (node (ref "USB-TTL") (pin "SHLD6") (pinfunction "SHLD_SHLD6") (pintype "bidirectional"))
      (node (ref "USB-TTL") (pin "SHLD7") (pinfunction "SHLD_SHLD7") (pintype "bidirectional"))
      (node (ref "USB-TTL") (pin "SHLD8") (pinfunction "SHLD_SHLD8") (pintype "bidirectional"))
      (node (ref "X1") (pin "2") (pinfunction "G2_2") (pintype "power_in"))
      (node (ref "X1") (pin "4") (pinfunction "G1_4") (pintype "power_in"))
    )
    (net (code "52") (name "Net-(D1-PadA)") (class "Default")
      (node (ref "D1") (pin "A") (pinfunction "A_A") (pintype "passive"))
      (node (ref "R15") (pin "2") (pinfunction "2_2") (pintype "passive"))
    )
    (net (code "53") (name "Net-(D2-PadA)") (class "Default")
      (node (ref "D2") (pin "A") (pinfunction "A_A") (pintype "passive"))
      (node (ref "R20") (pin "2") (pinfunction "2_2") (pintype "passive"))
    )
    (net (code "54") (name "Net-(D3-PadA)") (class "Default")
      (node (ref "D3") (pin "A") (pinfunction "A_A") (pintype "passive"))
      (node (ref "R43") (pin "2") (pinfunction "2_2") (pintype "passive"))
    )
    (net (code "55") (name "Net-(D4-PadA)") (class "Default")
      (node (ref "D4") (pin "A") (pinfunction "A_A") (pintype "passive"))
      (node (ref "R21") (pin "2") (pinfunction "2_2") (pintype "passive"))
    )
    (net (code "56") (name "Net-(D5-PadA)") (class "Default")
      (node (ref "D5") (pin "A") (pinfunction "A_A") (pintype "passive"))
      (node (ref "R22") (pin "2") (pinfunction "2_2") (pintype "passive"))
    )
    (net (code "57") (name "Net-(D8-PadC)") (class "Default")
      (node (ref "D8") (pin "C") (pinfunction "C_C") (pintype "passive"))
      (node (ref "R28") (pin "1") (pinfunction "1_1") (pintype "passive"))
    )
    (net (code "58") (name "Net-(D9-PadC)") (class "Default")
      (node (ref "D9") (pin "C") (pinfunction "C_C") (pintype "passive"))
      (node (ref "R29") (pin "1") (pinfunction "1_1") (pintype "passive"))
    )
    (net (code "59") (name "Net-(OLED1-C1N)") (class "Default")
      (node (ref "C27") (pin "2") (pinfunction "2_2") (pintype "passive"))
      (node (ref "OLED1") (pin "5") (pinfunction "C1N_5") (pintype "bidirectional"))
    )
    (net (code "60") (name "Net-(OLED1-C1P)") (class "Default")
      (node (ref "C27") (pin "1") (pinfunction "1_1") (pintype "passive"))
      (node (ref "OLED1") (pin "4") (pinfunction "C1P_4") (pintype "bidirectional"))
    )
    (net (code "61") (name "Net-(OLED1-C2N)") (class "Default")
      (node (ref "C26") (pin "2") (pinfunction "2_2") (pintype "passive"))
      (node (ref "OLED1") (pin "3") (pinfunction "C2N_3") (pintype "bidirectional"))
    )
    (net (code "62") (name "Net-(OLED1-C2P)") (class "Default")
      (node (ref "C26") (pin "1") (pinfunction "1_1") (pintype "passive"))
      (node (ref "OLED1") (pin "2") (pinfunction "C2P_2") (pintype "bidirectional"))
    )
    (net (code "63") (name "Net-(OLED1-D{slash}C#)") (class "Default")
      (node (ref "OLED1") (pin "15") (pinfunction "D/C#_15") (pintype "bidirectional"))
      (node (ref "R25") (pin "1") (pinfunction "1_1") (pintype "passive"))
      (node (ref "R5") (pin "1") (pinfunction "1_1") (pintype "passive"))
    )
    (net (code "64") (name "Net-(OLED1-IREF)") (class "Default")
      (node (ref "OLED1") (pin "26") (pinfunction "IREF_26") (pintype "bidirectional"))
      (node (ref "R26") (pin "1") (pinfunction "1_1") (pintype "passive"))
    )
    (net (code "65") (name "Net-(OLED1-RES#)") (class "Default")
      (node (ref "C17") (pin "2") (pinfunction "2_2") (pintype "passive"))
      (node (ref "D7") (pin "+") (pinfunction "+_+") (pintype "passive"))
      (node (ref "OLED1") (pin "14") (pinfunction "RES#_14") (pintype "bidirectional"))
      (node (ref "R1") (pin "1") (pinfunction "1_1") (pintype "passive"))
    )
    (net (code "66") (name "Net-(OLED1-VCC)") (class "Default")
      (node (ref "C29") (pin "2") (pinfunction "2_2") (pintype "passive"))
      (node (ref "OLED1") (pin "28") (pinfunction "VCC_28") (pintype "bidirectional"))
    )
    (net (code "67") (name "Net-(OLED1-VCOMH)") (class "Default")
      (node (ref "C28") (pin "2") (pinfunction "2_2") (pintype "passive"))
      (node (ref "OLED1") (pin "27") (pinfunction "VCOMH_27") (pintype "bidirectional"))
    )
    (net (code "68") (name "Net-(PWR-PadC)") (class "Default")
      (node (ref "PWR") (pin "C") (pinfunction "C_C") (pintype "passive"))
      (node (ref "R3") (pin "2") (pinfunction "2_2") (pintype "passive"))
    )
    (net (code "69") (name "Net-(Q1-G)") (class "Default")
      (node (ref "Q1") (pin "1") (pinfunction "G_1") (pintype "passive"))
      (node (ref "Q13") (pin "3") (pinfunction "C_3") (pintype "passive"))
      (node (ref "R40") (pin "2") (pinfunction "2_2") (pintype "passive"))
    )
    (net (code "70") (name "Net-(Q6-G)") (class "Default")
      (node (ref "Q6") (pin "1") (pinfunction "G_1") (pintype "passive"))
      (node (ref "Q9") (pin "3") (pinfunction "C_3") (pintype "passive"))
      (node (ref "R173") (pin "2") (pinfunction "2_2") (pintype "passive"))
    )
    (net (code "71") (name "Net-(Q8-B)") (class "Default")
      (node (ref "Q8") (pin "1") (pinfunction "B_1") (pintype "passive"))
      (node (ref "Q8") (pin "3") (pinfunction "C_3") (pintype "passive"))
      (node (ref "Q9") (pin "1") (pinfunction "B_1") (pintype "passive"))
      (node (ref "R172") (pin "2") (pinfunction "2_2") (pintype "passive"))
    )
    (net (code "72") (name "Net-(Q10-B)") (class "Default")
      (node (ref "Q10") (pin "1") (pinfunction "B_1") (pintype "passive"))
      (node (ref "Q10") (pin "3") (pinfunction "C_3") (pintype "passive"))
      (node (ref "Q11") (pin "1") (pinfunction "B_1") (pintype "passive"))
      (node (ref "R10") (pin "2") (pinfunction "2_2") (pintype "passive"))
    )
    (net (code "73") (name "Net-(Q11-C)") (class "Default")
      (node (ref "Q11") (pin "3") (pinfunction "C_3") (pintype "passive"))
      (node (ref "Q7") (pin "1") (pinfunction "G_1") (pintype "passive"))
      (node (ref "R39") (pin "2") (pinfunction "2_2") (pintype "passive"))
    )
    (net (code "74") (name "Net-(Q12-B)") (class "Default")
      (node (ref "Q12") (pin "1") (pinfunction "B_1") (pintype "passive"))
      (node (ref "Q12") (pin "3") (pinfunction "C_3") (pintype "passive"))
      (node (ref "Q13") (pin "1") (pinfunction "B_1") (pintype "passive"))
      (node (ref "R24") (pin "2") (pinfunction "2_2") (pintype "passive"))
    )
    (net (code "75") (name "Net-(U2-EXTON)") (class "Default")
      (node (ref "R13") (pin "1") (pinfunction "1_1") (pintype "passive"))
      (node (ref "U2") (pin "1") (pinfunction "EXTON_1") (pintype "bidirectional"))
    )
    (net (code "76") (name "Net-(U2-RSTN)") (class "Default")
      (node (ref "R19") (pin "1") (pinfunction "1_1") (pintype "passive"))
      (node (ref "U2") (pin "3") (pinfunction "RSTN_3") (pintype "bidirectional"))
    )
    (net (code "77") (name "Net-(U2-WAKEUP)") (class "Default")
      (node (ref "R8") (pin "1") (pinfunction "1_1") (pintype "passive"))
      (node (ref "U2") (pin "2") (pinfunction "WAKEUP_2") (pintype "bidirectional"))
    )
    (net (code "78") (name "Net-(U5-1-VBAT)") (class "Default")
      (node (ref "R45") (pin "2") (pinfunction "2_2") (pintype "passive"))
      (node (ref "U5") (pin "1") (pinfunction "1-VBAT_1") (pintype "bidirectional"))
    )
    (net (code "79") (name "Net-(U6-CHRG)") (class "Default")
      (node (ref "R28") (pin "2") (pinfunction "2_2") (pintype "passive"))
      (node (ref "U6") (pin "7") (pinfunction "CHRG_7") (pintype "bidirectional"))
    )
    (net (code "80") (name "Net-(U6-DONE)") (class "Default")
      (node (ref "R29") (pin "2") (pinfunction "2_2") (pintype "passive"))
      (node (ref "U6") (pin "6") (pinfunction "DONE_6") (pintype "bidirectional"))
    )
    (net (code "81") (name "Net-(U6-ISET)") (class "Default")
      (node (ref "R27") (pin "1") (pinfunction "1_1") (pintype "passive"))
      (node (ref "U6") (pin "2") (pinfunction "ISET_2") (pintype "bidirectional"))
    )
    (net (code "82") (name "Net-(U7-RXD)") (class "Default")
      (node (ref "R38") (pin "2") (pinfunction "2_2") (pintype "passive"))
      (node (ref "U7") (pin "9") (pinfunction "RXD_9") (pintype "bidirectional"))
    )
    (net (code "83") (name "Net-(U7-TXD)") (class "Default")
      (node (ref "R37") (pin "2") (pinfunction "2_2") (pintype "passive"))
      (node (ref "U7") (pin "8") (pinfunction "TXD_8") (pintype "bidirectional"))
    )
    (net (code "84") (name "Net-(USB-NATIVE-CC1)") (class "Default")
      (node (ref "R36") (pin "2") (pinfunction "2_2") (pintype "passive"))
      (node (ref "USB-NATIVE") (pin "A5") (pinfunction "CC1_A5") (pintype "bidirectional"))
    )
    (net (code "85") (name "Net-(USB-NATIVE-CC2)") (class "Default")
      (node (ref "R35") (pin "2") (pinfunction "2_2") (pintype "passive"))
      (node (ref "USB-NATIVE") (pin "B5") (pinfunction "CC2_B5") (pintype "bidirectional"))
    )
    (net (code "86") (name "Net-(USB-TTL-CC1)") (class "Default")
      (node (ref "R31") (pin "2") (pinfunction "2_2") (pintype "passive"))
      (node (ref "USB-TTL") (pin "A5") (pinfunction "CC1_A5") (pintype "bidirectional"))
    )
    (net (code "87") (name "Net-(USB-TTL-CC2)") (class "Default")
      (node (ref "R30") (pin "2") (pinfunction "2_2") (pintype "passive"))
      (node (ref "USB-TTL") (pin "B5") (pinfunction "CC2_B5") (pintype "bidirectional"))
    )
    (net (code "88") (name "VBUS") (class "Default")
      (node (ref "C1") (pin "1") (pinfunction "1_1") (pintype "passive"))
      (node (ref "C14") (pin "2") (pinfunction "2_2") (pintype "passive"))
      (node (ref "C170") (pin "1") (pinfunction "1_1") (pintype "passive"))
      (node (ref "C171") (pin "1") (pinfunction "1_1") (pintype "passive"))
      (node (ref "C18") (pin "1") (pinfunction "1_1") (pintype "passive"))
      (node (ref "C19") (pin "1") (pinfunction "1_1") (pintype "passive"))
      (node (ref "C2") (pin "1") (pinfunction "1_1") (pintype "passive"))
      (node (ref "C23") (pin "2") (pinfunction "2_2") (pintype "passive"))
      (node (ref "C9") (pin "2") (pinfunction "2_2") (pintype "passive"))
      (node (ref "D8") (pin "A") (pinfunction "A_A") (pintype "passive"))
      (node (ref "D9") (pin "A") (pinfunction "A_A") (pintype "passive"))
      (node (ref "Q1") (pin "2") (pinfunction "S_2") (pintype "passive"))
      (node (ref "Q13") (pin "2") (pinfunction "E_2") (pintype "passive"))
      (node (ref "Q6") (pin "3") (pinfunction "D_3") (pintype "passive"))
      (node (ref "Q8") (pin "2") (pinfunction "E_2") (pintype "passive"))
      (node (ref "U6") (pin "4") (pinfunction "VIN_4") (pintype "bidirectional"))
      (node (ref "U6") (pin "8") (pinfunction "CE_8") (pintype "bidirectional"))
      (node (ref "USB-NATIVE") (pin "VBUS1") (pinfunction "VBUS_VBUS1") (pintype "bidirectional"))
      (node (ref "USB-NATIVE") (pin "VBUS2") (pinfunction "VBUS_VBUS2") (pintype "bidirectional"))
    )
    (net (code "89") (name "unconnected-(OLED1-NC-Pad7)") (class "Default")
      (node (ref "OLED1") (pin "7") (pinfunction "NC_7") (pintype "bidirectional"))
    )
    (net (code "90") (name "unconnected-(U2-GPIO5-Pad10)") (class "Default")
      (node (ref "U2") (pin "10") (pinfunction "GPIO5_10") (pintype "bidirectional"))
    )
    (net (code "91") (name "unconnected-(U2-GPIO6-Pad9)") (class "Default")
      (node (ref "U2") (pin "9") (pinfunction "GPIO6_9") (pintype "bidirectional"))
    )
    (net (code "92") (name "unconnected-(U2-GPOI4-Pad11)") (class "Default")
      (node (ref "U2") (pin "11") (pinfunction "GPOI4_11") (pintype "bidirectional"))
    )
    (net (code "93") (name "unconnected-(U5-PB3-39-Pad39)") (class "Default")
      (node (ref "U5") (pin "39") (pinfunction "PB3-39_39") (pintype "bidirectional"))
    )
    (net (code "94") (name "unconnected-(U5-PB4-40-Pad40)") (class "Default")
      (node (ref "U5") (pin "40") (pinfunction "PB4-40_40") (pintype "bidirectional"))
    )
    (net (code "95") (name "unconnected-(U5-PB8-45-Pad45)") (class "Default")
      (node (ref "U5") (pin "45") (pinfunction "PB8-45_45") (pintype "bidirectional"))
    )
    (net (code "96") (name "unconnected-(U5-PB9-46-Pad46)") (class "Default")
      (node (ref "U5") (pin "46") (pinfunction "PB9-46_46") (pintype "bidirectional"))
    )
    (net (code "97") (name "unconnected-(U7-CTS#-Pad5)") (class "Default")
      (node (ref "U7") (pin "5") (pinfunction "CTS#_5") (pintype "bidirectional"))
    )
  )
)
